# Auxilary.net
KiCad netlist of a schematic drawn in Altium Designer
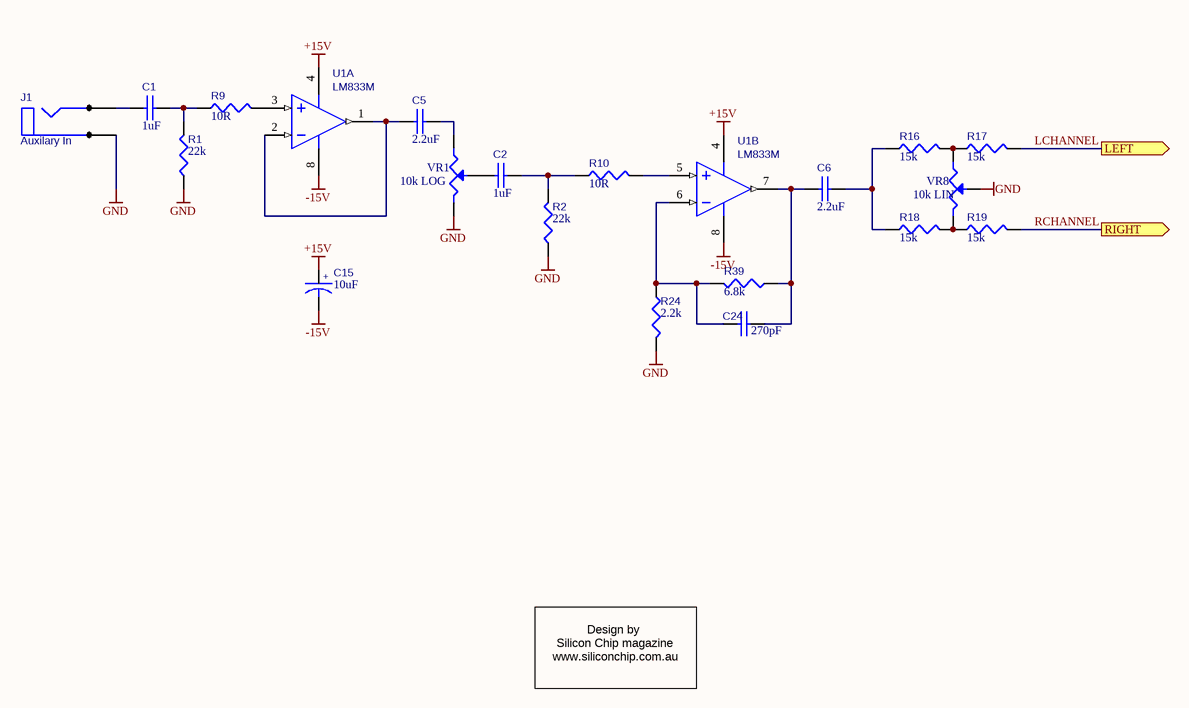
[diagram p0: Auxilary.SchDoc]

(export (version "E")
  (design (tool "Eeschema 10.0.6"))
  (components
    (comp (ref "C1")
      (value "1uF")
      (footprint "RB.2/.4-NP")
      (description "Capacitor")
      (libsource (lib "*") (part "CAP"))
    )
    (comp (ref "C2")
      (value "1uF")
      (footprint "RB.2/.4-NP")
      (description "Capacitor")
      (libsource (lib "*") (part "CAP"))
    )
    (comp (ref "C5")
      (value "2.2uF")
      (footprint "RB.2/.4-NP")
      (description "Capacitor")
      (libsource (lib "*") (part "CAP"))
    )
    (comp (ref "C6")
      (value "2.2uF")
      (footprint "RB.2/.4-NP")
      (description "Capacitor")
      (libsource (lib "*") (part "CAP"))
    )
    (comp (ref "C15")
      (value "10uF")
      (footprint "RB.2/.4")
      (description "Bi-Polar Capacitor")
      (libsource (lib "*") (part "CAPACITOR POL"))
    )
    (comp (ref "C24")
      (value "270pF")
      (footprint "RAD0.2")
      (description "Capacitor")
      (libsource (lib "*") (part "CAP"))
    )
    (comp (ref "J1")
      (value "Auxilary In")
      (footprint "JACK-6.25MM")
      (libsource (lib "*") (part "PHONEJACK MONO"))
    )
    (comp (ref "R1")
      (value "22k")
      (footprint "AXIAL0.4")
      (description "Resistor")
      (libsource (lib "") (part "RES1_1"))
    )
    (comp (ref "R2")
      (value "22k")
      (footprint "AXIAL0.4")
      (description "Resistor")
      (libsource (lib "") (part "RES1_1"))
    )
    (comp (ref "R9")
      (value "10R")
      (footprint "AXIAL0.4")
      (description "Resistor")
      (libsource (lib "*") (part "RES1"))
    )
    (comp (ref "R10")
      (value "10R")
      (footprint "AXIAL0.4")
      (description "Resistor")
      (libsource (lib "*") (part "RES1"))
    )
    (comp (ref "R16")
      (value "15k")
      (footprint "AXIAL0.4")
      (description "Resistor")
      (libsource (lib "*") (part "RES1"))
    )
    (comp (ref "R17")
      (value "15k")
      (footprint "AXIAL0.4")
      (description "Resistor")
      (libsource (lib "*") (part "RES1"))
    )
    (comp (ref "R18")
      (value "15k")
      (footprint "AXIAL0.4")
      (description "Resistor")
      (libsource (lib "*") (part "RES1"))
    )
    (comp (ref "R19")
      (value "15k")
      (footprint "AXIAL0.4")
      (description "Resistor")
      (libsource (lib "*") (part "RES1"))
    )
    (comp (ref "R24")
      (value "2.2k")
      (footprint "AXIAL0.4")
      (description "Resistor")
      (libsource (lib "") (part "RES1_3"))
    )
    (comp (ref "R39")
      (value "6.8k")
      (footprint "AXIAL0.4")
      (description "Resistor")
      (libsource (lib "") (part "RES1_2"))
    )
    (comp (ref "U1")
      (value "LM833M")
      (footprint "DIP8")
      (description "Fast Settling Dual Operational Amplifier")
      (libsource (lib "*") (part "LM833M"))
    )
    (comp (ref "VR1")
      (value "10k LOG")
      (footprint "POT - 24MM")
      (description "Potentiometer")
      (libsource (lib "*") (part "POT1"))
    )
    (comp (ref "VR8")
      (value "10k LIN")
      (footprint "POT - 24MM")
      (description "Potentiometer")
      (libsource (lib "*") (part "POT1"))
    )
  )
  (nets
    (net (code "1") (name "+15V") (class "Default")
      (node (ref "C15") (pin "1") (pinfunction "1_1") (pintype "passive"))
      (node (ref "U1") (pin "4") (pinfunction "V-_4") (pintype "power_in"))
    )
    (net (code "2") (name "-15V") (class "Default")
      (node (ref "C15") (pin "2") (pinfunction "2_2") (pintype "passive"))
      (node (ref "U1") (pin "8") (pinfunction "V+_8") (pintype "power_in"))
    )
    (net (code "3") (name "/LCHANNEL") (class "Default")
      (node (ref "R17") (pin "2") (pinfunction "2_2") (pintype "passive"))
    )
    (net (code "4") (name "/RCHANNEL") (class "Default")
      (node (ref "R19") (pin "2") (pinfunction "2_2") (pintype "passive"))
    )
    (net (code "5") (name "GND") (class "Default")
      (node (ref "J1") (pin "3") (pinfunction "C_3") (pintype "passive"))
      (node (ref "R1") (pin "1") (pinfunction "1_1") (pintype "passive"))
      (node (ref "R2") (pin "1") (pinfunction "1_1") (pintype "passive"))
      (node (ref "R24") (pin "2") (pinfunction "2_2") (pintype "passive"))
      (node (ref "VR1") (pin "3") (pinfunction "3_3") (pintype "passive"))
      (node (ref "VR8") (pin "2") (pinfunction "W_2") (pintype "passive"))
    )
    (net (code "6") (name "Net-(C1-Pad2)") (class "Default")
      (node (ref "C1") (pin "2") (pinfunction "2_2") (pintype "passive"))
      (node (ref "R1") (pin "2") (pinfunction "2_2") (pintype "passive"))
      (node (ref "R9") (pin "1") (pinfunction "1_1") (pintype "passive"))
    )
    (net (code "7") (name "Net-(C2-Pad2)") (class "Default")
      (node (ref "C2") (pin "2") (pinfunction "2_2") (pintype "passive"))
      (node (ref "R10") (pin "1") (pinfunction "1_1") (pintype "passive"))
      (node (ref "R2") (pin "2") (pinfunction "2_2") (pintype "passive"))
    )
    (net (code "8") (name "Net-(C5-Pad2)") (class "Default")
      (node (ref "C5") (pin "2") (pinfunction "2_2") (pintype "passive"))
      (node (ref "VR1") (pin "1") (pinfunction "1_1") (pintype "passive"))
    )
    (net (code "9") (name "Net-(C6-Pad2)") (class "Default")
      (node (ref "C6") (pin "2") (pinfunction "2_2") (pintype "passive"))
      (node (ref "R16") (pin "1") (pinfunction "1_1") (pintype "passive"))
      (node (ref "R18") (pin "1") (pinfunction "1_1") (pintype "passive"))
    )
    (net (code "10") (name "Net-(J1-A)") (class "Default")
      (node (ref "C1") (pin "1") (pinfunction "1_1") (pintype "passive"))
      (node (ref "J1") (pin "1") (pinfunction "A_1") (pintype "passive"))
    )
    (net (code "11") (name "Net-(R16-Pad2)") (class "Default")
      (node (ref "R16") (pin "2") (pinfunction "2_2") (pintype "passive"))
      (node (ref "R17") (pin "1") (pinfunction "1_1") (pintype "passive"))
      (node (ref "VR8") (pin "1") (pinfunction "1_1") (pintype "passive"))
    )
    (net (code "12") (name "Net-(R18-Pad2)") (class "Default")
      (node (ref "R18") (pin "2") (pinfunction "2_2") (pintype "passive"))
      (node (ref "R19") (pin "1") (pinfunction "1_1") (pintype "passive"))
      (node (ref "VR8") (pin "3") (pinfunction "3_3") (pintype "passive"))
    )
    (net (code "13") (name "Net-(U1A-IN1+)") (class "Default")
      (node (ref "R9") (pin "2") (pinfunction "2_2") (pintype "passive"))
      (node (ref "U1") (pin "3") (pinfunction "IN1+_3") (pintype "input"))
    )
    (net (code "14") (name "Net-(U1A-IN1-)") (class "Default")
      (node (ref "C5") (pin "1") (pinfunction "1_1") (pintype "passive"))
      (node (ref "U1") (pin "1") (pinfunction "OUT1_1") (pintype "output"))
      (node (ref "U1") (pin "2") (pinfunction "IN1-_2") (pintype "input"))
    )
    (net (code "15") (name "Net-(U1B-IN2+)") (class "Default")
      (node (ref "R10") (pin "2") (pinfunction "2_2") (pintype "passive"))
      (node (ref "U1") (pin "5") (pinfunction "IN2+_5") (pintype "input"))
    )
    (net (code "16") (name "Net-(U1B-IN2-)") (class "Default")
      (node (ref "C24") (pin "1") (pinfunction "1_1") (pintype "passive"))
      (node (ref "R24") (pin "1") (pinfunction "1_1") (pintype "passive"))
      (node (ref "R39") (pin "2") (pinfunction "2_2") (pintype "passive"))
      (node (ref "U1") (pin "6") (pinfunction "IN2-_6") (pintype "input"))
    )
    (net (code "17") (name "Net-(U1B-OUT2)") (class "Default")
      (node (ref "C24") (pin "2") (pinfunction "2_2") (pintype "passive"))
      (node (ref "C6") (pin "1") (pinfunction "1_1") (pintype "passive"))
      (node (ref "R39") (pin "1") (pinfunction "1_1") (pintype "passive"))
      (node (ref "U1") (pin "7") (pinfunction "OUT2_7") (pintype "output"))
    )
    (net (code "18") (name "Net-(VR1-W)") (class "Default")
      (node (ref "C2") (pin "1") (pinfunction "1_1") (pintype "passive"))
      (node (ref "VR1") (pin "2") (pinfunction "W_2") (pintype "passive"))
    )
  )
)
